# ProPrj_acoustic_imager_2026-03-04-rev1.net
KiCad netlist of a schematic drawn in EasyEDA Pro
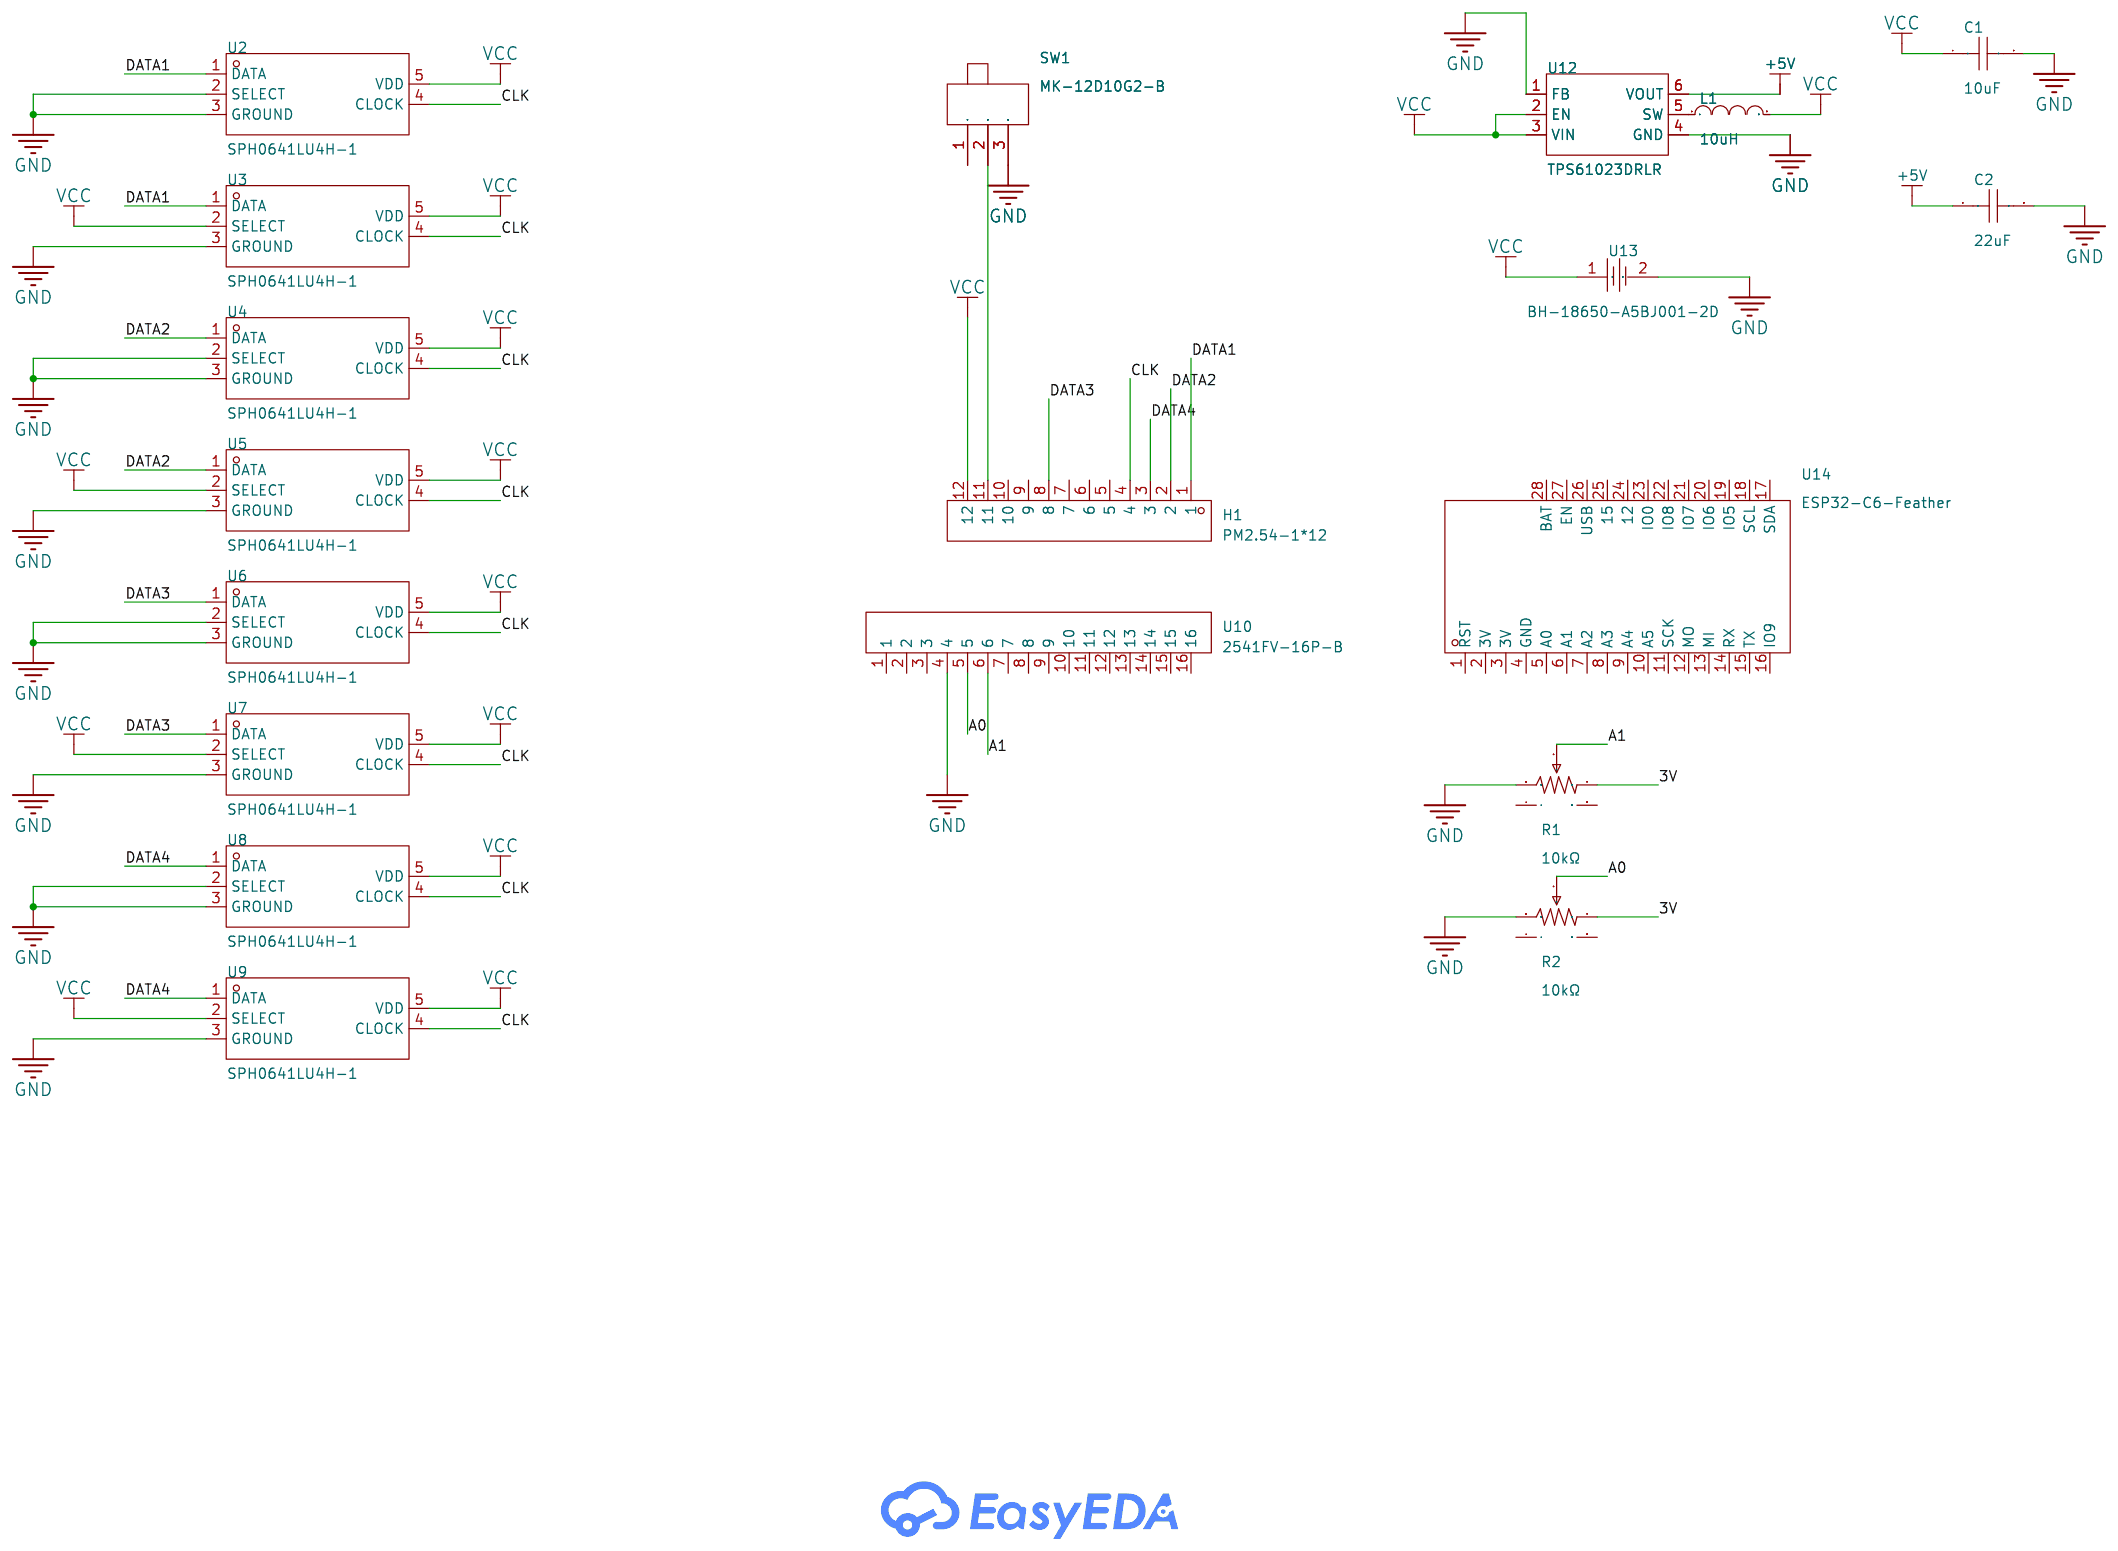
[diagram p0: schematic sheet]

(export (version "E")
  (design (tool "Eeschema 10.0.6"))
  (components
    (comp (ref "C1")
      (value "10uF")
      (footprint "easyedapro:C0805")
      (description "Capacitance:10uF Tolerance:±10% Tolerance:±10% Voltage Rating:50V Temperature Coefficient:X5R")
      (fields
        (field (name "Manufacturer Part") "GRM21BR61H106KE43L")
        (field (name "Manufacturer") "muRata(村田)")
      )
      (libsource (lib "easyedapro") (part "GRM21BR61H106KE43L"))
    )
    (comp (ref "C2")
      (value "22uF")
      (footprint "easyedapro:C0805")
      (description "Capacitance:22uF Tolerance:±20% Tolerance:±20% Voltage Rating:10V Temperature Coefficient:X7R")
      (fields
        (field (name "Manufacturer Part") "GRM21BZ71A226ME15K")
        (field (name "Manufacturer") "muRata(村田)")
      )
      (libsource (lib "easyedapro") (part "GRM21BZ71A226ME15K"))
    )
    (comp (ref "H1")
      (value "PM2.54-1*12")
      (footprint "easyedapro:HDR-TH_12P-P2.54-V-F")
      (fields (field (name "Manufacturer") "ZHOURI(洲日)"))
      (libsource (lib "easyedapro") (part "PM2.54-1*12"))
    )
    (comp (ref "L1")
      (value "10uH")
      (footprint "easyedapro:L0805")
      (fields
        (field (name "Manufacturer Part") "SDFL2012S100KTF")
        (field (name "Manufacturer") "Sunlord(顺络)")
      )
      (libsource (lib "easyedapro") (part "SDFL2012S100KTF"))
    )
    (comp (ref "R1")
      (value "10kΩ")
      (footprint "easyedapro:SW-TH_PTV09A-4015F-B502")
      (fields (field (name "Manufacturer Part") "PTV09A-4025F-B103") (field (name "Manufacturer") "BOURNS"))
      (libsource (lib "easyedapro") (part "PTV09A-4025F-B103"))
    )
    (comp (ref "R2")
      (value "10kΩ")
      (footprint "easyedapro:SW-TH_PTV09A-4015F-B502")
      (fields (field (name "Manufacturer Part") "PTV09A-4025F-B103") (field (name "Manufacturer") "BOURNS"))
      (libsource (lib "easyedapro") (part "PTV09A-4025F-B103"))
    )
    (comp (ref "SW1")
      (value "MK-12D10G2-B")
      (footprint "easyedapro:SW-TH_MK-12D10G2-B")
      (fields (field (name "Manufacturer") "HOOYA(皓宇电子)"))
      (libsource (lib "easyedapro") (part "MK-12D10G2-B"))
    )
    (comp (ref "U2")
      (value "SPH0641LU4H-1")
      (footprint "easyedapro:MIC-SMD_5P_L3.5-W2.7-P0.82_SPH0641LU4H-1")
      (fields (field (name "Manufacturer") "Knowles(楼氏)"))
      (libsource (lib "easyedapro") (part "SPH0641LU4H-1"))
    )
    (comp (ref "U3")
      (value "SPH0641LU4H-1")
      (footprint "easyedapro:MIC-SMD_5P_L3.5-W2.7-P0.82_SPH0641LU4H-1")
      (fields (field (name "Manufacturer") "Knowles(楼氏)"))
      (libsource (lib "easyedapro") (part "SPH0641LU4H-1"))
    )
    (comp (ref "U4")
      (value "SPH0641LU4H-1")
      (footprint "easyedapro:MIC-SMD_5P_L3.5-W2.7-P0.82_SPH0641LU4H-1")
      (fields (field (name "Manufacturer") "Knowles(楼氏)"))
      (libsource (lib "easyedapro") (part "SPH0641LU4H-1"))
    )
    (comp (ref "U5")
      (value "SPH0641LU4H-1")
      (footprint "easyedapro:MIC-SMD_5P_L3.5-W2.7-P0.82_SPH0641LU4H-1")
      (fields (field (name "Manufacturer") "Knowles(楼氏)"))
      (libsource (lib "easyedapro") (part "SPH0641LU4H-1"))
    )
    (comp (ref "U6")
      (value "SPH0641LU4H-1")
      (footprint "easyedapro:MIC-SMD_5P_L3.5-W2.7-P0.82_SPH0641LU4H-1")
      (fields (field (name "Manufacturer") "Knowles(楼氏)"))
      (libsource (lib "easyedapro") (part "SPH0641LU4H-1"))
    )
    (comp (ref "U7")
      (value "SPH0641LU4H-1")
      (footprint "easyedapro:MIC-SMD_5P_L3.5-W2.7-P0.82_SPH0641LU4H-1")
      (fields (field (name "Manufacturer") "Knowles(楼氏)"))
      (libsource (lib "easyedapro") (part "SPH0641LU4H-1"))
    )
    (comp (ref "U8")
      (value "SPH0641LU4H-1")
      (footprint "easyedapro:MIC-SMD_5P_L3.5-W2.7-P0.82_SPH0641LU4H-1")
      (fields (field (name "Manufacturer") "Knowles(楼氏)"))
      (libsource (lib "easyedapro") (part "SPH0641LU4H-1"))
    )
    (comp (ref "U9")
      (value "SPH0641LU4H-1")
      (footprint "easyedapro:MIC-SMD_5P_L3.5-W2.7-P0.82_SPH0641LU4H-1")
      (fields (field (name "Manufacturer") "Knowles(楼氏)"))
      (libsource (lib "easyedapro") (part "SPH0641LU4H-1"))
    )
    (comp (ref "U10")
      (value "2541FV-16P-B")
      (footprint "easyedapro:HDR-TH_16P-P2.54-V-F-4")
      (fields (field (name "Manufacturer") "HanElectricity(瀚源)"))
      (libsource (lib "easyedapro") (part "2541FV-16P-B"))
    )
    (comp (ref "U12")
      (value "TPS61023DRLR")
      (footprint "easyedapro:SOT-563_L1.6-W1.2-P0.50-LS1.6-BR")
      (fields (field (name "Manufacturer") "TI(德州仪器)"))
      (libsource (lib "easyedapro") (part "TPS61023DRLR"))
    )
    (comp (ref "U13")
      (value "BH-18650-A5BJ001-2D")
      (footprint "easyedapro:BAT-TH_BH-18650-A5BJ001-2D")
      (description "Type:Battery holder Operating Temperature:-10~100°C Contact coating:Nickel plated")
      (fields (field (name "Manufacturer") "MYOUNG(美阳)"))
      (libsource (lib "easyedapro") (part "BH-18650-A5BJ001-2D"))
    )
    (comp (ref "U14")
      (value "ESP32-C6-Feather")
      (footprint "easyedapro:COMM-TH_L50.8-W22.9-P2.54-LS20.32")
      (libsource (lib "easyedapro") (part "ESP32-C6-FEATHER"))
    )
  )
  (nets
    (net (code "1") (name "+5V") (class "Default")
      (node (ref "C2") (pin "1") (pinfunction "1_1") (pintype "unspecified"))
      (node (ref "U12") (pin "6") (pinfunction "VOUT_6") (pintype "unspecified"))
    )
    (net (code "2") (name "/3V") (class "Default")
      (node (ref "R1") (pin "1") (pinfunction "1_1") (pintype "unspecified"))
      (node (ref "R2") (pin "1") (pinfunction "1_1") (pintype "unspecified"))
    )
    (net (code "3") (name "/A0") (class "Default")
      (node (ref "R2") (pin "2") (pinfunction "2_2") (pintype "unspecified"))
      (node (ref "U10") (pin "5") (pinfunction "5_5") (pintype "unspecified"))
    )
    (net (code "4") (name "/A1") (class "Default")
      (node (ref "R1") (pin "2") (pinfunction "2_2") (pintype "unspecified"))
      (node (ref "U10") (pin "6") (pinfunction "6_6") (pintype "unspecified"))
    )
    (net (code "5") (name "/CLK") (class "Default")
      (node (ref "H1") (pin "4") (pinfunction "4_4") (pintype "unspecified"))
      (node (ref "U2") (pin "4") (pinfunction "CLOCK_4") (pintype "unspecified"))
      (node (ref "U3") (pin "4") (pinfunction "CLOCK_4") (pintype "unspecified"))
      (node (ref "U4") (pin "4") (pinfunction "CLOCK_4") (pintype "unspecified"))
      (node (ref "U5") (pin "4") (pinfunction "CLOCK_4") (pintype "unspecified"))
      (node (ref "U6") (pin "4") (pinfunction "CLOCK_4") (pintype "unspecified"))
      (node (ref "U7") (pin "4") (pinfunction "CLOCK_4") (pintype "unspecified"))
      (node (ref "U8") (pin "4") (pinfunction "CLOCK_4") (pintype "unspecified"))
      (node (ref "U9") (pin "4") (pinfunction "CLOCK_4") (pintype "unspecified"))
    )
    (net (code "6") (name "/DATA1") (class "Default")
      (node (ref "H1") (pin "1") (pinfunction "1_1") (pintype "unspecified"))
      (node (ref "U2") (pin "1") (pinfunction "DATA_1") (pintype "unspecified"))
      (node (ref "U3") (pin "1") (pinfunction "DATA_1") (pintype "unspecified"))
    )
    (net (code "7") (name "/DATA2") (class "Default")
      (node (ref "H1") (pin "2") (pinfunction "2_2") (pintype "unspecified"))
      (node (ref "U4") (pin "1") (pinfunction "DATA_1") (pintype "unspecified"))
      (node (ref "U5") (pin "1") (pinfunction "DATA_1") (pintype "unspecified"))
    )
    (net (code "8") (name "/DATA3") (class "Default")
      (node (ref "H1") (pin "8") (pinfunction "8_8") (pintype "unspecified"))
      (node (ref "U6") (pin "1") (pinfunction "DATA_1") (pintype "unspecified"))
      (node (ref "U7") (pin "1") (pinfunction "DATA_1") (pintype "unspecified"))
    )
    (net (code "9") (name "/DATA4") (class "Default")
      (node (ref "H1") (pin "3") (pinfunction "3_3") (pintype "unspecified"))
      (node (ref "U8") (pin "1") (pinfunction "DATA_1") (pintype "unspecified"))
      (node (ref "U9") (pin "1") (pinfunction "DATA_1") (pintype "unspecified"))
    )
    (net (code "10") (name "GND") (class "Default")
      (node (ref "C1") (pin "2") (pinfunction "2_2") (pintype "unspecified"))
      (node (ref "C2") (pin "2") (pinfunction "2_2") (pintype "unspecified"))
      (node (ref "R1") (pin "3") (pinfunction "3_3") (pintype "unspecified"))
      (node (ref "R2") (pin "3") (pinfunction "3_3") (pintype "unspecified"))
      (node (ref "SW1") (pin "3") (pinfunction "3_3") (pintype "unspecified"))
      (node (ref "U10") (pin "4") (pinfunction "4_4") (pintype "unspecified"))
      (node (ref "U12") (pin "1") (pinfunction "FB_1") (pintype "unspecified"))
      (node (ref "U12") (pin "4") (pinfunction "GND_4") (pintype "unspecified"))
      (node (ref "U13") (pin "2") (pinfunction "2_2") (pintype "input"))
      (node (ref "U2") (pin "2") (pinfunction "SELECT_2") (pintype "unspecified"))
      (node (ref "U2") (pin "3") (pinfunction "GROUND_3") (pintype "unspecified"))
      (node (ref "U3") (pin "3") (pinfunction "GROUND_3") (pintype "unspecified"))
      (node (ref "U4") (pin "2") (pinfunction "SELECT_2") (pintype "unspecified"))
      (node (ref "U4") (pin "3") (pinfunction "GROUND_3") (pintype "unspecified"))
      (node (ref "U5") (pin "3") (pinfunction "GROUND_3") (pintype "unspecified"))
      (node (ref "U6") (pin "2") (pinfunction "SELECT_2") (pintype "unspecified"))
      (node (ref "U6") (pin "3") (pinfunction "GROUND_3") (pintype "unspecified"))
      (node (ref "U7") (pin "3") (pinfunction "GROUND_3") (pintype "unspecified"))
      (node (ref "U8") (pin "2") (pinfunction "SELECT_2") (pintype "unspecified"))
      (node (ref "U8") (pin "3") (pinfunction "GROUND_3") (pintype "unspecified"))
      (node (ref "U9") (pin "3") (pinfunction "GROUND_3") (pintype "unspecified"))
    )
    (net (code "11") (name "Net-(H1-Pad11)") (class "Default")
      (node (ref "H1") (pin "11") (pinfunction "11_11") (pintype "unspecified"))
      (node (ref "SW1") (pin "2") (pinfunction "2_2") (pintype "unspecified"))
    )
    (net (code "12") (name "Net-(U12-SW)") (class "Default")
      (node (ref "L1") (pin "1") (pinfunction "1_1") (pintype "unspecified"))
      (node (ref "U12") (pin "5") (pinfunction "SW_5") (pintype "unspecified"))
    )
    (net (code "13") (name "VCC") (class "Default")
      (node (ref "C1") (pin "1") (pinfunction "1_1") (pintype "unspecified"))
      (node (ref "H1") (pin "12") (pinfunction "12_12") (pintype "unspecified"))
      (node (ref "L1") (pin "2") (pinfunction "2_2") (pintype "unspecified"))
      (node (ref "U12") (pin "2") (pinfunction "EN_2") (pintype "unspecified"))
      (node (ref "U12") (pin "3") (pinfunction "VIN_3") (pintype "unspecified"))
      (node (ref "U13") (pin "1") (pinfunction "1_1") (pintype "input"))
      (node (ref "U2") (pin "5") (pinfunction "VDD_5") (pintype "unspecified"))
      (node (ref "U3") (pin "2") (pinfunction "SELECT_2") (pintype "unspecified"))
      (node (ref "U3") (pin "5") (pinfunction "VDD_5") (pintype "unspecified"))
      (node (ref "U4") (pin "5") (pinfunction "VDD_5") (pintype "unspecified"))
      (node (ref "U5") (pin "2") (pinfunction "SELECT_2") (pintype "unspecified"))
      (node (ref "U5") (pin "5") (pinfunction "VDD_5") (pintype "unspecified"))
      (node (ref "U6") (pin "5") (pinfunction "VDD_5") (pintype "unspecified"))
      (node (ref "U7") (pin "2") (pinfunction "SELECT_2") (pintype "unspecified"))
      (node (ref "U7") (pin "5") (pinfunction "VDD_5") (pintype "unspecified"))
      (node (ref "U8") (pin "5") (pinfunction "VDD_5") (pintype "unspecified"))
      (node (ref "U9") (pin "2") (pinfunction "SELECT_2") (pintype "unspecified"))
      (node (ref "U9") (pin "5") (pinfunction "VDD_5") (pintype "unspecified"))
    )
    (net (code "14") (name "unconnected-(H1-Pad5)") (class "Default")
      (node (ref "H1") (pin "5") (pinfunction "5_5") (pintype "unspecified"))
    )
    (net (code "15") (name "unconnected-(H1-Pad6)") (class "Default")
      (node (ref "H1") (pin "6") (pinfunction "6_6") (pintype "unspecified"))
    )
    (net (code "16") (name "unconnected-(H1-Pad7)") (class "Default")
      (node (ref "H1") (pin "7") (pinfunction "7_7") (pintype "unspecified"))
    )
    (net (code "17") (name "unconnected-(H1-Pad9)") (class "Default")
      (node (ref "H1") (pin "9") (pinfunction "9_9") (pintype "unspecified"))
    )
    (net (code "18") (name "unconnected-(H1-Pad10)") (class "Default")
      (node (ref "H1") (pin "10") (pinfunction "10_10") (pintype "unspecified"))
    )
    (net (code "19") (name "unconnected-(R1-Pad4)") (class "Default")
      (node (ref "R1") (pin "4") (pinfunction "4_4") (pintype "unspecified"))
    )
    (net (code "20") (name "unconnected-(R1-Pad5)") (class "Default")
      (node (ref "R1") (pin "5") (pinfunction "5_5") (pintype "unspecified"))
    )
    (net (code "21") (name "unconnected-(R2-Pad4)") (class "Default")
      (node (ref "R2") (pin "4") (pinfunction "4_4") (pintype "unspecified"))
    )
    (net (code "22") (name "unconnected-(R2-Pad5)") (class "Default")
      (node (ref "R2") (pin "5") (pinfunction "5_5") (pintype "unspecified"))
    )
    (net (code "23") (name "unconnected-(SW1-Pad1)") (class "Default")
      (node (ref "SW1") (pin "1") (pinfunction "1_1") (pintype "unspecified"))
    )
    (net (code "24") (name "unconnected-(U10-Pad1)") (class "Default")
      (node (ref "U10") (pin "1") (pinfunction "1_1") (pintype "unspecified"))
    )
    (net (code "25") (name "unconnected-(U10-Pad2)") (class "Default")
      (node (ref "U10") (pin "2") (pinfunction "2_2") (pintype "unspecified"))
    )
    (net (code "26") (name "unconnected-(U10-Pad3)") (class "Default")
      (node (ref "U10") (pin "3") (pinfunction "3_3") (pintype "unspecified"))
    )
    (net (code "27") (name "unconnected-(U10-Pad7)") (class "Default")
      (node (ref "U10") (pin "7") (pinfunction "7_7") (pintype "unspecified"))
    )
    (net (code "28") (name "unconnected-(U10-Pad8)") (class "Default")
      (node (ref "U10") (pin "8") (pinfunction "8_8") (pintype "unspecified"))
    )
    (net (code "29") (name "unconnected-(U10-Pad9)") (class "Default")
      (node (ref "U10") (pin "9") (pinfunction "9_9") (pintype "unspecified"))
    )
    (net (code "30") (name "unconnected-(U10-Pad10)") (class "Default")
      (node (ref "U10") (pin "10") (pinfunction "10_10") (pintype "unspecified"))
    )
    (net (code "31") (name "unconnected-(U10-Pad11)") (class "Default")
      (node (ref "U10") (pin "11") (pinfunction "11_11") (pintype "unspecified"))
    )
    (net (code "32") (name "unconnected-(U10-Pad12)") (class "Default")
      (node (ref "U10") (pin "12") (pinfunction "12_12") (pintype "unspecified"))
    )
    (net (code "33") (name "unconnected-(U10-Pad13)") (class "Default")
      (node (ref "U10") (pin "13") (pinfunction "13_13") (pintype "unspecified"))
    )
    (net (code "34") (name "unconnected-(U10-Pad14)") (class "Default")
      (node (ref "U10") (pin "14") (pinfunction "14_14") (pintype "unspecified"))
    )
    (net (code "35") (name "unconnected-(U10-Pad15)") (class "Default")
      (node (ref "U10") (pin "15") (pinfunction "15_15") (pintype "unspecified"))
    )
    (net (code "36") (name "unconnected-(U10-Pad16)") (class "Default")
      (node (ref "U10") (pin "16") (pinfunction "16_16") (pintype "unspecified"))
    )
    (net (code "37") (name "unconnected-(U14-3V-Pad2)") (class "Default")
      (node (ref "U14") (pin "2") (pinfunction "3V_2") (pintype "unspecified"))
    )
    (net (code "38") (name "unconnected-(U14-3V-Pad3)") (class "Default")
      (node (ref "U14") (pin "3") (pinfunction "3V_3") (pintype "unspecified"))
    )
    (net (code "39") (name "unconnected-(U14-12-Pad24)") (class "Default")
      (node (ref "U14") (pin "24") (pinfunction "12_24") (pintype "unspecified"))
    )
    (net (code "40") (name "unconnected-(U14-15-Pad25)") (class "Default")
      (node (ref "U14") (pin "25") (pinfunction "15_25") (pintype "unspecified"))
    )
    (net (code "41") (name "unconnected-(U14-A0-Pad5)") (class "Default")
      (node (ref "U14") (pin "5") (pinfunction "A0_5") (pintype "unspecified"))
    )
    (net (code "42") (name "unconnected-(U14-A1-Pad6)") (class "Default")
      (node (ref "U14") (pin "6") (pinfunction "A1_6") (pintype "unspecified"))
    )
    (net (code "43") (name "unconnected-(U14-A2-Pad7)") (class "Default")
      (node (ref "U14") (pin "7") (pinfunction "A2_7") (pintype "unspecified"))
    )
    (net (code "44") (name "unconnected-(U14-A3-Pad8)") (class "Default")
      (node (ref "U14") (pin "8") (pinfunction "A3_8") (pintype "unspecified"))
    )
    (net (code "45") (name "unconnected-(U14-A4-Pad9)") (class "Default")
      (node (ref "U14") (pin "9") (pinfunction "A4_9") (pintype "unspecified"))
    )
    (net (code "46") (name "unconnected-(U14-A5-Pad10)") (class "Default")
      (node (ref "U14") (pin "10") (pinfunction "A5_10") (pintype "unspecified"))
    )
    (net (code "47") (name "unconnected-(U14-BAT-Pad28)") (class "Default")
      (node (ref "U14") (pin "28") (pinfunction "BAT_28") (pintype "unspecified"))
    )
    (net (code "48") (name "unconnected-(U14-EN-Pad27)") (class "Default")
      (node (ref "U14") (pin "27") (pinfunction "EN_27") (pintype "unspecified"))
    )
    (net (code "49") (name "unconnected-(U14-GND-Pad4)") (class "Default")
      (node (ref "U14") (pin "4") (pinfunction "GND_4") (pintype "unspecified"))
    )
    (net (code "50") (name "unconnected-(U14-IO0-Pad23)") (class "Default")
      (node (ref "U14") (pin "23") (pinfunction "IO0_23") (pintype "unspecified"))
    )
    (net (code "51") (name "unconnected-(U14-IO5-Pad19)") (class "Default")
      (node (ref "U14") (pin "19") (pinfunction "IO5_19") (pintype "unspecified"))
    )
    (net (code "52") (name "unconnected-(U14-IO6-Pad20)") (class "Default")
      (node (ref "U14") (pin "20") (pinfunction "IO6_20") (pintype "unspecified"))
    )
    (net (code "53") (name "unconnected-(U14-IO7-Pad21)") (class "Default")
      (node (ref "U14") (pin "21") (pinfunction "IO7_21") (pintype "unspecified"))
    )
    (net (code "54") (name "unconnected-(U14-IO8-Pad22)") (class "Default")
      (node (ref "U14") (pin "22") (pinfunction "IO8_22") (pintype "unspecified"))
    )
    (net (code "55") (name "unconnected-(U14-IO9-Pad16)") (class "Default")
      (node (ref "U14") (pin "16") (pinfunction "IO9_16") (pintype "unspecified"))
    )
    (net (code "56") (name "unconnected-(U14-MI-Pad13)") (class "Default")
      (node (ref "U14") (pin "13") (pinfunction "MI_13") (pintype "unspecified"))
    )
    (net (code "57") (name "unconnected-(U14-MO-Pad12)") (class "Default")
      (node (ref "U14") (pin "12") (pinfunction "MO_12") (pintype "unspecified"))
    )
    (net (code "58") (name "unconnected-(U14-RST-Pad1)") (class "Default")
      (node (ref "U14") (pin "1") (pinfunction "RST_1") (pintype "unspecified"))
    )
    (net (code "59") (name "unconnected-(U14-RX-Pad14)") (class "Default")
      (node (ref "U14") (pin "14") (pinfunction "RX_14") (pintype "unspecified"))
    )
    (net (code "60") (name "unconnected-(U14-SCK-Pad11)") (class "Default")
      (node (ref "U14") (pin "11") (pinfunction "SCK_11") (pintype "unspecified"))
    )
    (net (code "61") (name "unconnected-(U14-SCL-Pad18)") (class "Default")
      (node (ref "U14") (pin "18") (pinfunction "SCL_18") (pintype "unspecified"))
    )
    (net (code "62") (name "unconnected-(U14-SDA-Pad17)") (class "Default")
      (node (ref "U14") (pin "17") (pinfunction "SDA_17") (pintype "unspecified"))
    )
    (net (code "63") (name "unconnected-(U14-TX-Pad15)") (class "Default")
      (node (ref "U14") (pin "15") (pinfunction "TX_15") (pintype "unspecified"))
    )
    (net (code "64") (name "unconnected-(U14-USB-Pad26)") (class "Default")
      (node (ref "U14") (pin "26") (pinfunction "USB_26") (pintype "unspecified"))
    )
  )
)
